# ISS-Notify_Test-Harness.net
KiCad netlist of a schematic drawn in EAGLE
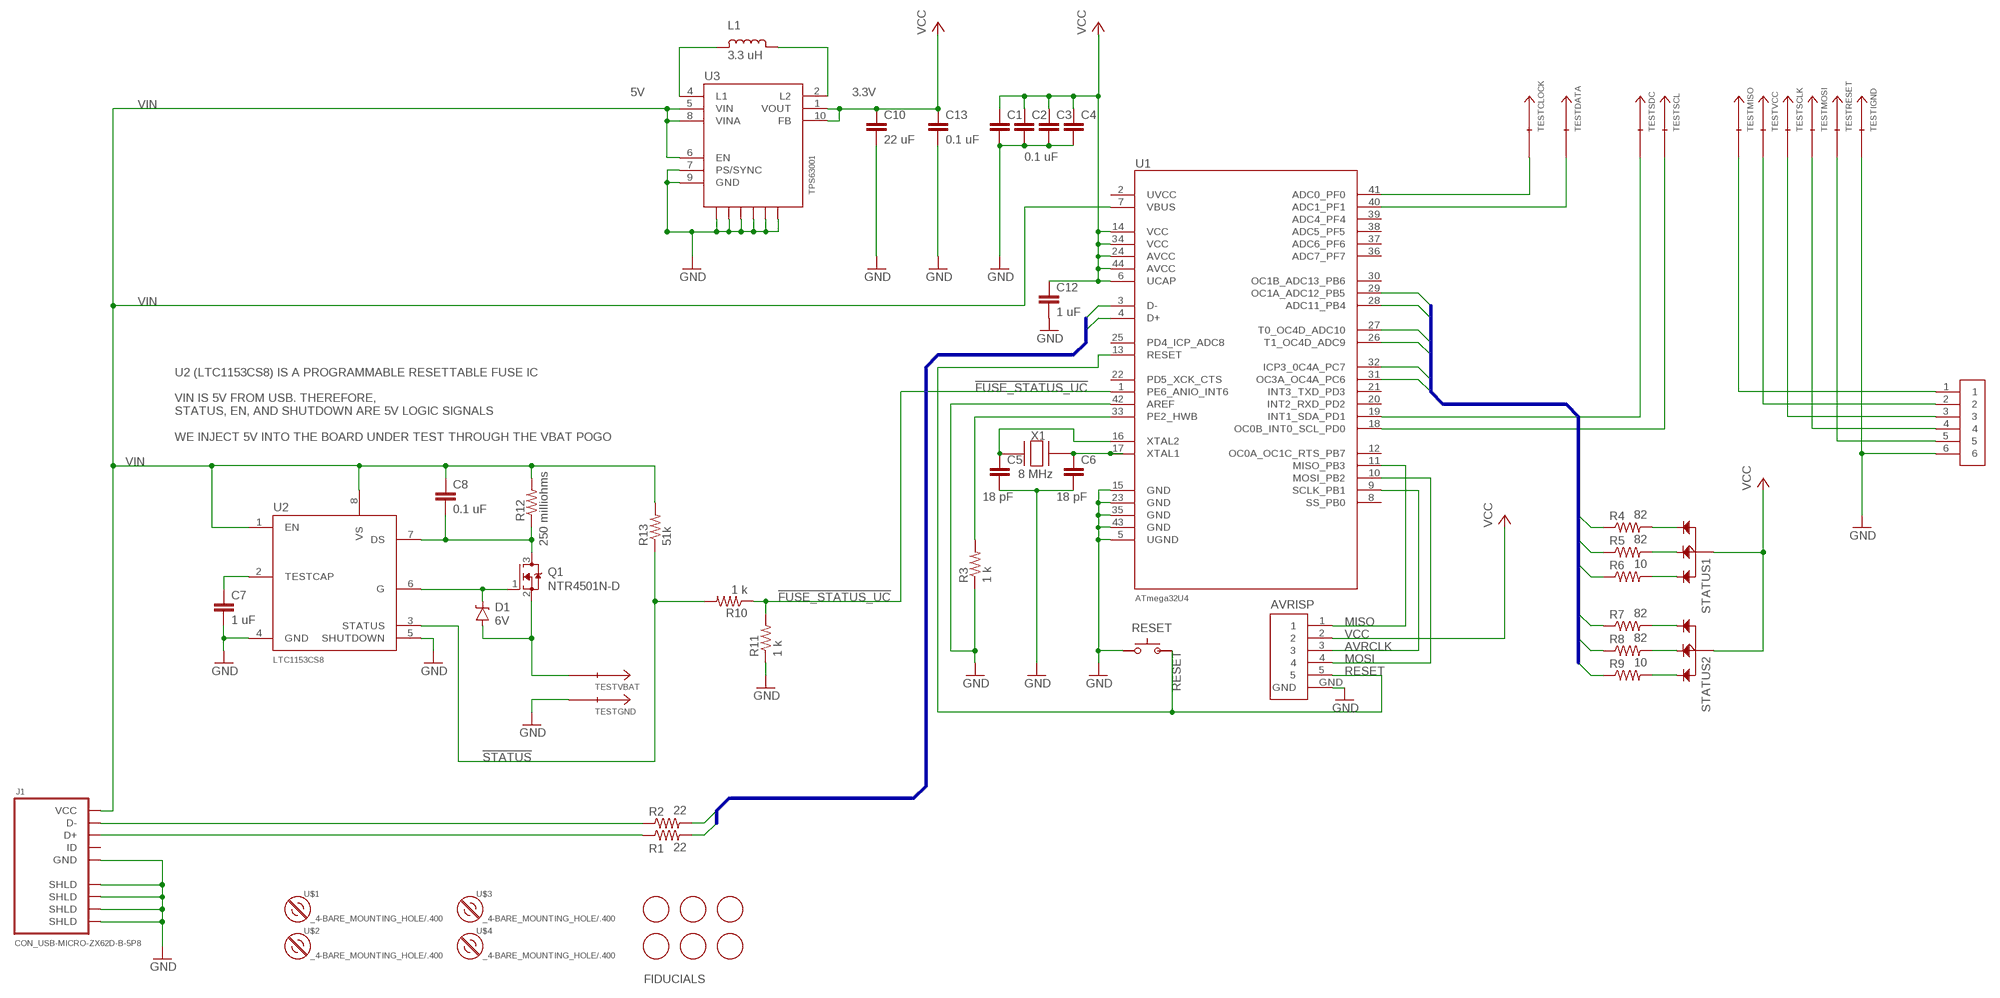
[diagram p0: schematic, sheet 1]

(export (version "E")
  (design (tool "Eeschema 10.0.6"))
  (components
    (comp (ref "AVRISP")
      (value "AVRISP")
      (footprint "eagle-import:AVRISP")
      (libsource (lib "eagle-import") (part "AVRISP"))
    )
    (comp (ref "C1")
      (value "0.1 uF")
      (footprint "eagle-import:0603-C-NOSILK")
      (libsource (lib "eagle-import") (part "C-EU0603-C-NOSILK"))
    )
    (comp (ref "C2")
      (value "0.1 uF")
      (footprint "eagle-import:0603-C-NOSILK")
      (libsource (lib "eagle-import") (part "C-EU0603-C-NOSILK"))
    )
    (comp (ref "C3")
      (value "0.1 uF")
      (footprint "eagle-import:0603-C-NOSILK")
      (libsource (lib "eagle-import") (part "C-EU0603-C-NOSILK"))
    )
    (comp (ref "C4")
      (value "0.1 uF")
      (footprint "eagle-import:0603-C-NOSILK")
      (libsource (lib "eagle-import") (part "C-EU0603-C-NOSILK"))
    )
    (comp (ref "C5")
      (value "18 pF")
      (footprint "eagle-import:0603-C-NOSILK")
      (libsource (lib "eagle-import") (part "C-EU0603-C-NOSILK"))
    )
    (comp (ref "C6")
      (value "18 pF")
      (footprint "eagle-import:0603-C-NOSILK")
      (libsource (lib "eagle-import") (part "C-EU0603-C-NOSILK"))
    )
    (comp (ref "C7")
      (value "1 uF")
      (footprint "eagle-import:0603-C-NOSILK")
      (libsource (lib "eagle-import") (part "C-EU0603-C-NOSILK"))
    )
    (comp (ref "C8")
      (value "0.1 uF")
      (footprint "eagle-import:0603-C-NOSILK")
      (libsource (lib "eagle-import") (part "C-EU0603-C-NOSILK"))
    )
    (comp (ref "C10")
      (value "22 uF")
      (footprint "eagle-import:0805-C-NOSILK")
      (libsource (lib "eagle-import") (part "C-EU0805-C-NOSILK"))
    )
    (comp (ref "C12")
      (value "1 uF")
      (footprint "eagle-import:0603-C-NOSILK")
      (libsource (lib "eagle-import") (part "C-EU0603-C-NOSILK"))
    )
    (comp (ref "C13")
      (value "0.1 uF")
      (footprint "eagle-import:0603-C-NOSILK")
      (libsource (lib "eagle-import") (part "C-EU0603-C-NOSILK"))
    )
    (comp (ref "D1")
      (value "6V")
      (footprint "eagle-import:SOD-323")
      (libsource (lib "eagle-import") (part "DIODE-ZENER3.3V"))
    )
    (comp (ref "F1")
      (value "FIDUCIAL")
      (footprint "eagle-import:FIDUCIAL_1MM")
      (libsource (lib "eagle-import") (part "FIDUCIAL"))
    )
    (comp (ref "F2")
      (value "FIDUCIAL")
      (footprint "eagle-import:FIDUCIAL_1MM")
      (libsource (lib "eagle-import") (part "FIDUCIAL"))
    )
    (comp (ref "F3")
      (value "FIDUCIAL")
      (footprint "eagle-import:FIDUCIAL_1MM")
      (libsource (lib "eagle-import") (part "FIDUCIAL"))
    )
    (comp (ref "F4")
      (value "FIDUCIAL")
      (footprint "eagle-import:FIDUCIAL_1MM")
      (libsource (lib "eagle-import") (part "FIDUCIAL"))
    )
    (comp (ref "F5")
      (value "FIDUCIAL")
      (footprint "eagle-import:FIDUCIAL_1MM")
      (libsource (lib "eagle-import") (part "FIDUCIAL"))
    )
    (comp (ref "F6")
      (value "FIDUCIAL")
      (footprint "eagle-import:FIDUCIAL_1MM")
      (libsource (lib "eagle-import") (part "FIDUCIAL"))
    )
    (comp (ref "J1")
      (value "CON_USB-MICRO-ZX62D-B-5P8")
      (footprint "eagle-import:USBMICROSMT-HIROSE")
      (libsource (lib "eagle-import") (part "CON_USB-MICRO-ZX62D-B-5P8"))
    )
    (comp (ref "JPROGRAMER")
      (value "6HEADER")
      (footprint "eagle-import:6HEAD")
      (libsource (lib "eagle-import") (part "6HEADER"))
    )
    (comp (ref "L1")
      (value "3.3 uH")
      (footprint "eagle-import:0805-C-NOSILK")
      (libsource (lib "eagle-import") (part "PWR_INDUCTOR"))
    )
    (comp (ref "Q1")
      (value "NTR4501N-D")
      (footprint "eagle-import:SOT-23")
      (libsource (lib "eagle-import") (part "NTR4501N-D"))
    )
    (comp (ref "R1")
      (value "22")
      (footprint "eagle-import:0603-C-NOSILK")
      (libsource (lib "eagle-import") (part "R-US_0603-C-NOSILK"))
    )
    (comp (ref "R2")
      (value "22")
      (footprint "eagle-import:0603-C-NOSILK")
      (libsource (lib "eagle-import") (part "R-US_0603-C-NOSILK"))
    )
    (comp (ref "R3")
      (value "1 k")
      (footprint "eagle-import:0603-C-NOSILK")
      (libsource (lib "eagle-import") (part "R-US_0603-C-NOSILK"))
    )
    (comp (ref "R4")
      (value "82")
      (footprint "eagle-import:0603-C-NOSILK")
      (libsource (lib "eagle-import") (part "R-US_0603-C-NOSILK"))
    )
    (comp (ref "R5")
      (value "82")
      (footprint "eagle-import:0603-C-NOSILK")
      (libsource (lib "eagle-import") (part "R-US_0603-C-NOSILK"))
    )
    (comp (ref "R6")
      (value "10")
      (footprint "eagle-import:0603-C-NOSILK")
      (libsource (lib "eagle-import") (part "R-US_0603-C-NOSILK"))
    )
    (comp (ref "R7")
      (value "82")
      (footprint "eagle-import:0603-C-NOSILK")
      (libsource (lib "eagle-import") (part "R-US_0603-C-NOSILK"))
    )
    (comp (ref "R8")
      (value "82")
      (footprint "eagle-import:0603-C-NOSILK")
      (libsource (lib "eagle-import") (part "R-US_0603-C-NOSILK"))
    )
    (comp (ref "R9")
      (value "10")
      (footprint "eagle-import:0603-C-NOSILK")
      (libsource (lib "eagle-import") (part "R-US_0603-C-NOSILK"))
    )
    (comp (ref "R10")
      (value "1 k")
      (footprint "eagle-import:0603-C-NOSILK")
      (libsource (lib "eagle-import") (part "R-US_0603-C-NOSILK"))
    )
    (comp (ref "R11")
      (value "1 k")
      (footprint "eagle-import:0603-C-NOSILK")
      (libsource (lib "eagle-import") (part "R-US_0603-C-NOSILK"))
    )
    (comp (ref "R12")
      (value "250 milliohms")
      (footprint "eagle-import:0603-C-NOSILK")
      (libsource (lib "eagle-import") (part "R-US_0603-C-NOSILK"))
    )
    (comp (ref "R13")
      (value "51k")
      (footprint "eagle-import:0603-C-NOSILK")
      (libsource (lib "eagle-import") (part "R-US_0603-C-NOSILK"))
    )
    (comp (ref "RESET")
      (value "SWITCH")
      (footprint "eagle-import:SWITCH")
      (libsource (lib "eagle-import") (part "SWITCH"))
    )
    (comp (ref "STATUS1")
      (value "RGBLED")
      (footprint "eagle-import:SMDRGBLED")
      (libsource (lib "eagle-import") (part "RGBLED"))
    )
    (comp (ref "STATUS2")
      (value "RGBLED")
      (footprint "eagle-import:SMDRGBLED")
      (libsource (lib "eagle-import") (part "RGBLED"))
    )
    (comp (ref "TESTCLOCK")
      (value "POGOPIN")
      (footprint "eagle-import:POGOPIN")
      (libsource (lib "eagle-import") (part "POGOPIN"))
    )
    (comp (ref "TESTDATA")
      (value "POGOPIN")
      (footprint "eagle-import:POGOPIN")
      (libsource (lib "eagle-import") (part "POGOPIN"))
    )
    (comp (ref "TESTGND")
      (value "POGOPIN")
      (footprint "eagle-import:POGOPIN")
      (libsource (lib "eagle-import") (part "POGOPIN"))
    )
    (comp (ref "TESTIGND")
      (value "POGOPIN")
      (footprint "eagle-import:POGOPIN")
      (libsource (lib "eagle-import") (part "POGOPIN"))
    )
    (comp (ref "TESTMISO")
      (value "POGOPIN")
      (footprint "eagle-import:POGOPIN")
      (libsource (lib "eagle-import") (part "POGOPIN"))
    )
    (comp (ref "TESTMOSI")
      (value "POGOPIN")
      (footprint "eagle-import:POGOPIN")
      (libsource (lib "eagle-import") (part "POGOPIN"))
    )
    (comp (ref "TESTRESET")
      (value "POGOPIN")
      (footprint "eagle-import:POGOPIN")
      (libsource (lib "eagle-import") (part "POGOPIN"))
    )
    (comp (ref "TESTSCL")
      (value "POGOPIN")
      (footprint "eagle-import:POGOPIN")
      (libsource (lib "eagle-import") (part "POGOPIN"))
    )
    (comp (ref "TESTSCLK")
      (value "POGOPIN")
      (footprint "eagle-import:POGOPIN")
      (libsource (lib "eagle-import") (part "POGOPIN"))
    )
    (comp (ref "TESTSDC")
      (value "POGOPIN")
      (footprint "eagle-import:POGOPIN")
      (libsource (lib "eagle-import") (part "POGOPIN"))
    )
    (comp (ref "TESTVBAT")
      (value "POGOPIN")
      (footprint "eagle-import:POGOPIN")
      (libsource (lib "eagle-import") (part "POGOPIN"))
    )
    (comp (ref "TESTVCC")
      (value "POGOPIN")
      (footprint "eagle-import:POGOPIN")
      (libsource (lib "eagle-import") (part "POGOPIN"))
    )
    (comp (ref "U$1")
      (value "_4-BARE_MOUNTING_HOLE/.400")
      (footprint "eagle-import:_4_.400-BARE+STD_TOOL_CLEARANCE")
      (libsource (lib "eagle-import") (part "_4-BARE_MOUNTING_HOLE/.400"))
    )
    (comp (ref "U$2")
      (value "_4-BARE_MOUNTING_HOLE/.400")
      (footprint "eagle-import:_4_.400-BARE+STD_TOOL_CLEARANCE")
      (libsource (lib "eagle-import") (part "_4-BARE_MOUNTING_HOLE/.400"))
    )
    (comp (ref "U$3")
      (value "_4-BARE_MOUNTING_HOLE/.400")
      (footprint "eagle-import:_4_.400-BARE+STD_TOOL_CLEARANCE")
      (libsource (lib "eagle-import") (part "_4-BARE_MOUNTING_HOLE/.400"))
    )
    (comp (ref "U$4")
      (value "_4-BARE_MOUNTING_HOLE/.400")
      (footprint "eagle-import:_4_.400-BARE+STD_TOOL_CLEARANCE")
      (libsource (lib "eagle-import") (part "_4-BARE_MOUNTING_HOLE/.400"))
    )
    (comp (ref "U1")
      (value "ATMEGA32U4")
      (footprint "eagle-import:TQFP-44")
      (libsource (lib "eagle-import") (part "ATMEGA32U4"))
    )
    (comp (ref "U2")
      (value "LTC1153CS8")
      (footprint "eagle-import:SO-8")
      (libsource (lib "eagle-import") (part "LTC1153CS8"))
    )
    (comp (ref "U3")
      (value "TPS63001")
      (footprint "eagle-import:QFN10")
      (libsource (lib "eagle-import") (part "TPS63001"))
    )
    (comp (ref "X1")
      (value "8 MHz")
      (footprint "eagle-import:CX5Z")
      (libsource (lib "eagle-import") (part "CX5Z"))
    )
  )
  (nets
    (net (code "1") (name "/AVRCLK") (class "Default")
      (node (ref "AVRISP") (pin "3") (pinfunction "3_3") (pintype "bidirectional"))
      (node (ref "U1") (pin "9") (pinfunction "SCLK_PB1_9") (pintype "bidirectional"))
    )
    (net (code "2") (name "/D+") (class "Default")
      (node (ref "R1") (pin "2") (pinfunction "2_2") (pintype "passive"))
      (node (ref "U1") (pin "4") (pinfunction "D+_4") (pintype "bidirectional"))
    )
    (net (code "3") (name "/D-") (class "Default")
      (node (ref "R2") (pin "2") (pinfunction "2_2") (pintype "passive"))
      (node (ref "U1") (pin "3") (pinfunction "D-_3") (pintype "bidirectional"))
    )
    (net (code "4") (name "/LED1_B") (class "Default")
      (node (ref "R6") (pin "1") (pinfunction "1_1") (pintype "passive"))
      (node (ref "U1") (pin "29") (pinfunction "OC1A_ADC12_PB5_29") (pintype "bidirectional"))
    )
    (net (code "5") (name "/LED1_G") (class "Default")
      (node (ref "R5") (pin "1") (pinfunction "1_1") (pintype "passive"))
      (node (ref "U1") (pin "32") (pinfunction "ICP3_0C4A_PC7_32") (pintype "bidirectional"))
    )
    (net (code "6") (name "/LED1_R") (class "Default")
      (node (ref "R4") (pin "1") (pinfunction "1_1") (pintype "passive"))
      (node (ref "U1") (pin "31") (pinfunction "OC3A_OC4A_PC6_31") (pintype "bidirectional"))
    )
    (net (code "7") (name "/LED2_B") (class "Default")
      (node (ref "R9") (pin "1") (pinfunction "1_1") (pintype "passive"))
      (node (ref "U1") (pin "26") (pinfunction "T1_OC4D_ADC9_26") (pintype "bidirectional"))
    )
    (net (code "8") (name "/LED2_G") (class "Default")
      (node (ref "R8") (pin "1") (pinfunction "1_1") (pintype "passive"))
      (node (ref "U1") (pin "28") (pinfunction "ADC11_PB4_28") (pintype "bidirectional"))
    )
    (net (code "9") (name "/LED2_R") (class "Default")
      (node (ref "R7") (pin "1") (pinfunction "1_1") (pintype "passive"))
      (node (ref "U1") (pin "27") (pinfunction "T0_OC4D_ADC10_27") (pintype "bidirectional"))
    )
    (net (code "10") (name "/MISO") (class "Default")
      (node (ref "AVRISP") (pin "1") (pinfunction "1_1") (pintype "bidirectional"))
      (node (ref "U1") (pin "11") (pinfunction "MISO_PB3_11") (pintype "bidirectional"))
    )
    (net (code "11") (name "/MOSI") (class "Default")
      (node (ref "AVRISP") (pin "4") (pinfunction "4_4") (pintype "bidirectional"))
      (node (ref "U1") (pin "10") (pinfunction "MOSI_PB2_10") (pintype "bidirectional"))
    )
    (net (code "12") (name "/RESET") (class "Default")
      (node (ref "AVRISP") (pin "5") (pinfunction "5_5") (pintype "bidirectional"))
      (node (ref "RESET") (pin "1") (pinfunction "1_1") (pintype "bidirectional"))
      (node (ref "U1") (pin "13") (pinfunction "RESET_13") (pintype "input"))
    )
    (net (code "13") (name "/UVCC") (class "Default")
      (node (ref "U1") (pin "2") (pinfunction "UVCC_2") (pintype "power_in"))
    )
    (net (code "14") (name "/VIN") (class "Default")
      (node (ref "C8") (pin "1") (pinfunction "1_1") (pintype "passive"))
      (node (ref "J1") (pin "P1") (pinfunction "VCC_P1") (pintype "power_in"))
      (node (ref "R12") (pin "2") (pinfunction "2_2") (pintype "passive"))
      (node (ref "R13") (pin "2") (pinfunction "2_2") (pintype "passive"))
      (node (ref "U1") (pin "7") (pinfunction "VBUS_7") (pintype "bidirectional"))
      (node (ref "U2") (pin "1") (pinfunction "EN_1") (pintype "bidirectional"))
      (node (ref "U2") (pin "8") (pinfunction "VS_8") (pintype "bidirectional"))
      (node (ref "U3") (pin "5") (pinfunction "VIN_5") (pintype "bidirectional"))
      (node (ref "U3") (pin "6") (pinfunction "EN_6") (pintype "bidirectional"))
      (node (ref "U3") (pin "8") (pinfunction "VINA_8") (pintype "bidirectional"))
    )
    (net (code "15") (name "/~{FUSE_STATUS_UC}") (class "Default")
      (node (ref "R10") (pin "1") (pinfunction "1_1") (pintype "passive"))
      (node (ref "R11") (pin "2") (pinfunction "2_2") (pintype "passive"))
      (node (ref "U1") (pin "1") (pinfunction "PE6_ANIO_INT6_1") (pintype "bidirectional"))
    )
    (net (code "16") (name "/~{STATUS}") (class "Default")
      (node (ref "R10") (pin "2") (pinfunction "2_2") (pintype "passive"))
      (node (ref "R13") (pin "1") (pinfunction "1_1") (pintype "passive"))
      (node (ref "U2") (pin "3") (pinfunction "STATUS_3") (pintype "bidirectional"))
    )
    (net (code "17") (name "GND") (class "Default")
      (node (ref "AVRISP") (pin "GND") (pinfunction "GND_GND") (pintype "power_in"))
      (node (ref "C1") (pin "2") (pinfunction "2_2") (pintype "passive"))
      (node (ref "C10") (pin "2") (pinfunction "2_2") (pintype "passive"))
      (node (ref "C12") (pin "2") (pinfunction "2_2") (pintype "passive"))
      (node (ref "C13") (pin "2") (pinfunction "2_2") (pintype "passive"))
      (node (ref "C2") (pin "2") (pinfunction "2_2") (pintype "passive"))
      (node (ref "C3") (pin "2") (pinfunction "2_2") (pintype "passive"))
      (node (ref "C4") (pin "2") (pinfunction "2_2") (pintype "passive"))
      (node (ref "C5") (pin "2") (pinfunction "2_2") (pintype "passive"))
      (node (ref "C6") (pin "2") (pinfunction "2_2") (pintype "passive"))
      (node (ref "C7") (pin "2") (pinfunction "2_2") (pintype "passive"))
      (node (ref "J1") (pin "P$1") (pinfunction "SHLD_P$1") (pintype "power_in"))
      (node (ref "J1") (pin "P$2") (pinfunction "SHLD_P$2") (pintype "power_in"))
      (node (ref "J1") (pin "P$3") (pinfunction "SHLD_P$3") (pintype "power_in"))
      (node (ref "J1") (pin "P$4") (pinfunction "SHLD_P$4") (pintype "power_in"))
      (node (ref "J1") (pin "P5") (pinfunction "GND_P5") (pintype "power_in"))
      (node (ref "JPROGRAMER") (pin "6") (pinfunction "6_6") (pintype "bidirectional"))
      (node (ref "R11") (pin "1") (pinfunction "1_1") (pintype "passive"))
      (node (ref "R3") (pin "1") (pinfunction "1_1") (pintype "passive"))
      (node (ref "RESET") (pin "3") (pinfunction "2_3") (pintype "bidirectional"))
      (node (ref "TESTGND") (pin "1") (pinfunction "TEST_1") (pintype "bidirectional"))
      (node (ref "TESTIGND") (pin "1") (pinfunction "TEST_1") (pintype "bidirectional"))
      (node (ref "U1") (pin "15") (pinfunction "GND_15") (pintype "power_in"))
      (node (ref "U1") (pin "23") (pinfunction "GND_23") (pintype "power_in"))
      (node (ref "U1") (pin "35") (pinfunction "GND_35") (pintype "power_in"))
      (node (ref "U1") (pin "42") (pinfunction "AREF_42") (pintype "input"))
      (node (ref "U1") (pin "43") (pinfunction "GND_43") (pintype "power_in"))
      (node (ref "U1") (pin "5") (pinfunction "UGND_5") (pintype "power_in"))
      (node (ref "U2") (pin "4") (pinfunction "GND_4") (pintype "bidirectional"))
      (node (ref "U2") (pin "5") (pinfunction "SHUTDOWN_5") (pintype "bidirectional"))
      (node (ref "U3") (pin "3") (pinfunction "PGND_3") (pintype "bidirectional"))
      (node (ref "U3") (pin "7") (pinfunction "PS/SYNC_7") (pintype "bidirectional"))
      (node (ref "U3") (pin "9") (pinfunction "GND_9") (pintype "bidirectional"))
      (node (ref "U3") (pin "PAD") (pinfunction "GNDPAD_PAD") (pintype "bidirectional"))
      (node (ref "U3") (pin "PGND1") (pinfunction "PGND1_PGND1") (pintype "bidirectional"))
      (node (ref "U3") (pin "PGND2") (pinfunction "PGND2_PGND2") (pintype "bidirectional"))
      (node (ref "U3") (pin "PGND3") (pinfunction "PGND3_PGND3") (pintype "bidirectional"))
      (node (ref "U3") (pin "PGND4") (pinfunction "PGND4_PGND4") (pintype "bidirectional"))
    )
    (net (code "18") (name "Net-(J1-D+)") (class "Default")
      (node (ref "J1") (pin "P3") (pinfunction "D+_P3") (pintype "bidirectional"))
      (node (ref "R1") (pin "1") (pinfunction "1_1") (pintype "passive"))
    )
    (net (code "19") (name "Net-(J1-D-)") (class "Default")
      (node (ref "J1") (pin "P2") (pinfunction "D-_P2") (pintype "bidirectional"))
      (node (ref "R2") (pin "1") (pinfunction "1_1") (pintype "passive"))
    )
    (net (code "20") (name "Net-(L1-A)") (class "Default")
      (node (ref "L1") (pin "1") (pinfunction "A_1") (pintype "bidirectional"))
      (node (ref "U3") (pin "4") (pinfunction "L1_4") (pintype "bidirectional"))
    )
    (net (code "21") (name "Net-(L1-C)") (class "Default")
      (node (ref "L1") (pin "2") (pinfunction "C_2") (pintype "bidirectional"))
      (node (ref "U3") (pin "2") (pinfunction "L2_2") (pintype "bidirectional"))
    )
    (net (code "22") (name "Net-(Q1-D)") (class "Default")
      (node (ref "C8") (pin "2") (pinfunction "2_2") (pintype "passive"))
      (node (ref "Q1") (pin "3") (pinfunction "D_3") (pintype "bidirectional"))
      (node (ref "R12") (pin "1") (pinfunction "1_1") (pintype "passive"))
      (node (ref "U2") (pin "7") (pinfunction "DS_7") (pintype "bidirectional"))
    )
    (net (code "23") (name "Net-(Q1-G)") (class "Default")
      (node (ref "D1") (pin "C") (pinfunction "C_C") (pintype "passive"))
      (node (ref "Q1") (pin "1") (pinfunction "G_1") (pintype "bidirectional"))
      (node (ref "U2") (pin "6") (pinfunction "G_6") (pintype "bidirectional"))
    )
    (net (code "24") (name "Net-(Q1-S)") (class "Default")
      (node (ref "D1") (pin "A") (pinfunction "A_A") (pintype "passive"))
      (node (ref "Q1") (pin "2") (pinfunction "S_2") (pintype "bidirectional"))
      (node (ref "TESTVBAT") (pin "1") (pinfunction "TEST_1") (pintype "bidirectional"))
    )
    (net (code "25") (name "Net-(STATUS1-B)") (class "Default")
      (node (ref "R6") (pin "2") (pinfunction "2_2") (pintype "passive"))
      (node (ref "STATUS1") (pin "BLUE") (pinfunction "B_BLUE") (pintype "bidirectional"))
    )
    (net (code "26") (name "Net-(STATUS1-G)") (class "Default")
      (node (ref "R5") (pin "2") (pinfunction "2_2") (pintype "passive"))
      (node (ref "STATUS1") (pin "GREEN") (pinfunction "G_GREEN") (pintype "bidirectional"))
    )
    (net (code "27") (name "Net-(STATUS1-R)") (class "Default")
      (node (ref "R4") (pin "2") (pinfunction "2_2") (pintype "passive"))
      (node (ref "STATUS1") (pin "RED") (pinfunction "R_RED") (pintype "bidirectional"))
    )
    (net (code "28") (name "Net-(STATUS2-B)") (class "Default")
      (node (ref "R9") (pin "2") (pinfunction "2_2") (pintype "passive"))
      (node (ref "STATUS2") (pin "BLUE") (pinfunction "B_BLUE") (pintype "bidirectional"))
    )
    (net (code "29") (name "Net-(STATUS2-G)") (class "Default")
      (node (ref "R8") (pin "2") (pinfunction "2_2") (pintype "passive"))
      (node (ref "STATUS2") (pin "GREEN") (pinfunction "G_GREEN") (pintype "bidirectional"))
    )
    (net (code "30") (name "Net-(STATUS2-R)") (class "Default")
      (node (ref "R7") (pin "2") (pinfunction "2_2") (pintype "passive"))
      (node (ref "STATUS2") (pin "RED") (pinfunction "R_RED") (pintype "bidirectional"))
    )
    (net (code "31") (name "Net-(TESTCLOCK-TEST)") (class "Default")
      (node (ref "TESTCLOCK") (pin "1") (pinfunction "TEST_1") (pintype "bidirectional"))
      (node (ref "U1") (pin "41") (pinfunction "ADC0_PF0_41") (pintype "bidirectional"))
    )
    (net (code "32") (name "Net-(TESTDATA-TEST)") (class "Default")
      (node (ref "TESTDATA") (pin "1") (pinfunction "TEST_1") (pintype "bidirectional"))
      (node (ref "U1") (pin "40") (pinfunction "ADC1_PF1_40") (pintype "bidirectional"))
    )
    (net (code "33") (name "Net-(TESTMISO-TEST)") (class "Default")
      (node (ref "JPROGRAMER") (pin "1") (pinfunction "1_1") (pintype "bidirectional"))
      (node (ref "TESTMISO") (pin "1") (pinfunction "TEST_1") (pintype "bidirectional"))
    )
    (net (code "34") (name "Net-(TESTMOSI-TEST)") (class "Default")
      (node (ref "JPROGRAMER") (pin "4") (pinfunction "4_4") (pintype "bidirectional"))
      (node (ref "TESTMOSI") (pin "1") (pinfunction "TEST_1") (pintype "bidirectional"))
    )
    (net (code "35") (name "Net-(TESTRESET-TEST)") (class "Default")
      (node (ref "JPROGRAMER") (pin "5") (pinfunction "5_5") (pintype "bidirectional"))
      (node (ref "TESTRESET") (pin "1") (pinfunction "TEST_1") (pintype "bidirectional"))
    )
    (net (code "36") (name "Net-(TESTSCL-TEST)") (class "Default")
      (node (ref "TESTSCL") (pin "1") (pinfunction "TEST_1") (pintype "bidirectional"))
      (node (ref "U1") (pin "18") (pinfunction "OC0B_INT0_SCL_PD0_18") (pintype "bidirectional"))
    )
    (net (code "37") (name "Net-(TESTSCLK-TEST)") (class "Default")
      (node (ref "JPROGRAMER") (pin "3") (pinfunction "3_3") (pintype "bidirectional"))
      (node (ref "TESTSCLK") (pin "1") (pinfunction "TEST_1") (pintype "bidirectional"))
    )
    (net (code "38") (name "Net-(TESTSDC-TEST)") (class "Default")
      (node (ref "TESTSDC") (pin "1") (pinfunction "TEST_1") (pintype "bidirectional"))
      (node (ref "U1") (pin "19") (pinfunction "INT1_SDA_PD1_19") (pintype "bidirectional"))
    )
    (net (code "39") (name "Net-(TESTVCC-TEST)") (class "Default")
      (node (ref "JPROGRAMER") (pin "2") (pinfunction "2_2") (pintype "bidirectional"))
      (node (ref "TESTVCC") (pin "1") (pinfunction "TEST_1") (pintype "bidirectional"))
    )
    (net (code "40") (name "Net-(U1-PE2_HWB)") (class "Default")
      (node (ref "R3") (pin "2") (pinfunction "2_2") (pintype "passive"))
      (node (ref "U1") (pin "33") (pinfunction "PE2_HWB_33") (pintype "bidirectional"))
    )
    (net (code "41") (name "Net-(U1-XTAL1)") (class "Default")
      (node (ref "C6") (pin "1") (pinfunction "1_1") (pintype "passive"))
      (node (ref "U1") (pin "17") (pinfunction "XTAL1_17") (pintype "tri_state"))
      (node (ref "X1") (pin "3") (pinfunction "2_3") (pintype "bidirectional"))
    )
    (net (code "42") (name "Net-(U1-XTAL2)") (class "Default")
      (node (ref "C5") (pin "1") (pinfunction "1_1") (pintype "passive"))
      (node (ref "U1") (pin "16") (pinfunction "XTAL2_16") (pintype "tri_state"))
      (node (ref "X1") (pin "1") (pinfunction "1_1") (pintype "bidirectional"))
    )
    (net (code "43") (name "Net-(U2-TESTCAP)") (class "Default")
      (node (ref "C7") (pin "1") (pinfunction "1_1") (pintype "passive"))
      (node (ref "U2") (pin "2") (pinfunction "TESTCAP_2") (pintype "bidirectional"))
    )
    (net (code "44") (name "VCC") (class "Default")
      (node (ref "AVRISP") (pin "2") (pinfunction "2_2") (pintype "bidirectional"))
      (node (ref "C1") (pin "1") (pinfunction "1_1") (pintype "passive"))
      (node (ref "C10") (pin "1") (pinfunction "1_1") (pintype "passive"))
      (node (ref "C12") (pin "1") (pinfunction "1_1") (pintype "passive"))
      (node (ref "C13") (pin "1") (pinfunction "1_1") (pintype "passive"))
      (node (ref "C2") (pin "1") (pinfunction "1_1") (pintype "passive"))
      (node (ref "C3") (pin "1") (pinfunction "1_1") (pintype "passive"))
      (node (ref "C4") (pin "1") (pinfunction "1_1") (pintype "passive"))
      (node (ref "STATUS1") (pin "ANODE") (pinfunction "ANODE_ANODE") (pintype "bidirectional"))
      (node (ref "STATUS2") (pin "ANODE") (pinfunction "ANODE_ANODE") (pintype "bidirectional"))
      (node (ref "U1") (pin "14") (pinfunction "VCC_14") (pintype "power_in"))
      (node (ref "U1") (pin "24") (pinfunction "AVCC_24") (pintype "power_in"))
      (node (ref "U1") (pin "34") (pinfunction "VCC_34") (pintype "power_in"))
      (node (ref "U1") (pin "44") (pinfunction "AVCC_44") (pintype "power_in"))
      (node (ref "U1") (pin "6") (pinfunction "UCAP_6") (pintype "bidirectional"))
      (node (ref "U3") (pin "1") (pinfunction "VOUT_1") (pintype "bidirectional"))
      (node (ref "U3") (pin "10") (pinfunction "FB_10") (pintype "bidirectional"))
    )
    (net (code "45") (name "unconnected-(J1-ID-PadP4)") (class "Default")
      (node (ref "J1") (pin "P4") (pinfunction "ID_P4") (pintype "bidirectional"))
    )
    (net (code "46") (name "unconnected-(U1-ADC4_PF4-Pad39)") (class "Default")
      (node (ref "U1") (pin "39") (pinfunction "ADC4_PF4_39") (pintype "bidirectional"))
    )
    (net (code "47") (name "unconnected-(U1-ADC5_PF5-Pad38)") (class "Default")
      (node (ref "U1") (pin "38") (pinfunction "ADC5_PF5_38") (pintype "bidirectional"))
    )
    (net (code "48") (name "unconnected-(U1-ADC6_PF6-Pad37)") (class "Default")
      (node (ref "U1") (pin "37") (pinfunction "ADC6_PF6_37") (pintype "bidirectional"))
    )
    (net (code "49") (name "unconnected-(U1-ADC7_PF7-Pad36)") (class "Default")
      (node (ref "U1") (pin "36") (pinfunction "ADC7_PF7_36") (pintype "bidirectional"))
    )
    (net (code "50") (name "unconnected-(U1-INT2_RXD_PD2-Pad20)") (class "Default")
      (node (ref "U1") (pin "20") (pinfunction "INT2_RXD_PD2_20") (pintype "bidirectional"))
    )
    (net (code "51") (name "unconnected-(U1-INT3_TXD_PD3-Pad21)") (class "Default")
      (node (ref "U1") (pin "21") (pinfunction "INT3_TXD_PD3_21") (pintype "bidirectional"))
    )
    (net (code "52") (name "unconnected-(U1-OC0A_OC1C_RTS_PB7-Pad12)") (class "Default")
      (node (ref "U1") (pin "12") (pinfunction "OC0A_OC1C_RTS_PB7_12") (pintype "bidirectional"))
    )
    (net (code "53") (name "unconnected-(U1-OC1B_ADC13_PB6-Pad30)") (class "Default")
      (node (ref "U1") (pin "30") (pinfunction "OC1B_ADC13_PB6_30") (pintype "bidirectional"))
    )
    (net (code "54") (name "unconnected-(U1-PD4_ICP_ADC8-Pad25)") (class "Default")
      (node (ref "U1") (pin "25") (pinfunction "PD4_ICP_ADC8_25") (pintype "bidirectional"))
    )
    (net (code "55") (name "unconnected-(U1-PD5_XCK_CTS-Pad22)") (class "Default")
      (node (ref "U1") (pin "22") (pinfunction "PD5_XCK_CTS_22") (pintype "bidirectional"))
    )
    (net (code "56") (name "unconnected-(U1-SS_PB0-Pad8)") (class "Default")
      (node (ref "U1") (pin "8") (pinfunction "SS_PB0_8") (pintype "bidirectional"))
    )
  )
)
